# Test.net
KiCad netlist of a schematic drawn in EasyEDA Pro
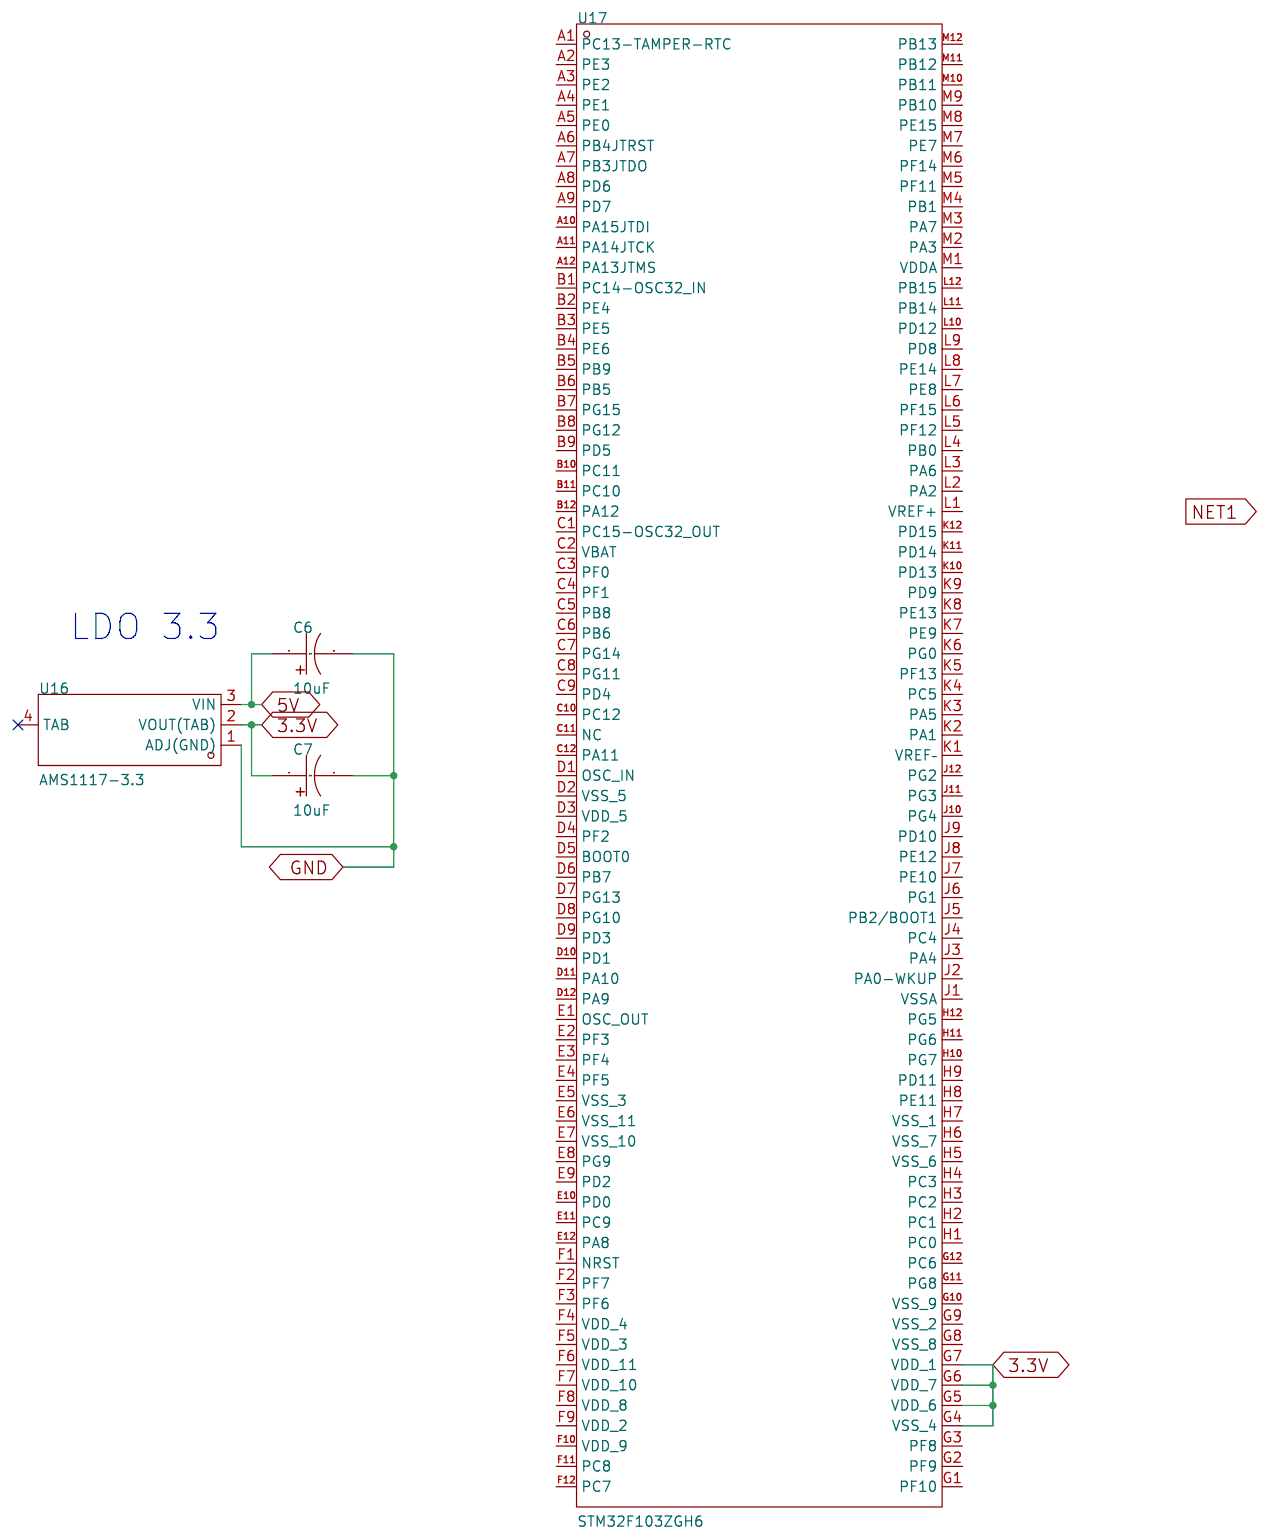
[diagram p0: schematic sheet]

(export (version "E")
  (design (tool "Eeschema 10.0.6"))
  (components
    (comp (ref "C6")
      (value "10uF")
      (footprint "easyedapro:CAP-SMD_BD4.0-L4.3-W4.3-FD-LS5.1")
      (fields (field (name "Manufacturer Part") "VSS100M1CTR-0404") (field (name "Manufacturer") "lelon(立隆)"))
      (libsource (lib "easyedapro") (part "VSS100M1C0404-TRO"))
    )
    (comp (ref "C7")
      (value "10uF")
      (footprint "easyedapro:CAP-SMD_BD4.0-L4.3-W4.3-FD-LS5.1")
      (fields (field (name "Manufacturer Part") "VSS100M1CTR-0404") (field (name "Manufacturer") "lelon(立隆)"))
      (libsource (lib "easyedapro") (part "VSS100M1C0404-TRO"))
    )
    (comp (ref "U16")
      (value "AMS1117-3.3")
      (footprint "easyedapro:SOT-223-4_L6.5-W3.5-P2.30-LS7.0-BR")
      (fields (field (name "Manufacturer") "UMW(友台半导体)"))
      (libsource (lib "easyedapro") (part "AMS1117-3.3_C347222"))
    )
    (comp (ref "U17")
      (value "STM32F103ZGH6")
      (footprint "easyedapro:CSPBGA-144_L10.0-W10.0-R12-C12-P0.80-TL")
      (fields (field (name "Manufacturer") "ST(意法半导体)"))
      (libsource (lib "easyedapro") (part "STM32F103ZGH6"))
    )
  )
  (nets
    (net (code "1") (name "3.3V") (class "Default")
      (node (ref "C7") (pin "1") (pinfunction "1_1") (pintype "unspecified"))
      (node (ref "U16") (pin "2") (pinfunction "VOUT(TAB)_2") (pintype "unspecified"))
      (node (ref "U17") (pin "G4") (pinfunction "VSS_4_G4") (pintype "unspecified"))
      (node (ref "U17") (pin "G5") (pinfunction "VDD_6_G5") (pintype "unspecified"))
      (node (ref "U17") (pin "G6") (pinfunction "VDD_7_G6") (pintype "unspecified"))
      (node (ref "U17") (pin "G7") (pinfunction "VDD_1_G7") (pintype "unspecified"))
    )
    (net (code "2") (name "5V") (class "Default")
      (node (ref "C6") (pin "1") (pinfunction "1_1") (pintype "unspecified"))
      (node (ref "U16") (pin "3") (pinfunction "VIN_3") (pintype "unspecified"))
    )
    (net (code "3") (name "GND") (class "Default")
      (node (ref "C6") (pin "2") (pinfunction "2_2") (pintype "unspecified"))
      (node (ref "C7") (pin "2") (pinfunction "2_2") (pintype "unspecified"))
      (node (ref "U16") (pin "1") (pinfunction "ADJ(GND)_1") (pintype "unspecified"))
    )
    (net (code "5") (name "unconnected-(U16-TAB-Pad4)") (class "Default")
      (node (ref "U16") (pin "4") (pinfunction "TAB_4") (pintype "unspecified+no_connect"))
    )
    (net (code "6") (name "unconnected-(U17-BOOT0-PadD5)") (class "Default")
      (node (ref "U17") (pin "D5") (pinfunction "BOOT0_D5") (pintype "unspecified"))
    )
    (net (code "7") (name "unconnected-(U17-NC-PadC11)") (class "Default")
      (node (ref "U17") (pin "C11") (pinfunction "NC_C11") (pintype "unspecified"))
    )
    (net (code "8") (name "unconnected-(U17-NRST-PadF1)") (class "Default")
      (node (ref "U17") (pin "F1") (pinfunction "NRST_F1") (pintype "unspecified"))
    )
    (net (code "9") (name "unconnected-(U17-OSC_IN-PadD1)") (class "Default")
      (node (ref "U17") (pin "D1") (pinfunction "OSC_IN_D1") (pintype "unspecified"))
    )
    (net (code "10") (name "unconnected-(U17-OSC_OUT-PadE1)") (class "Default")
      (node (ref "U17") (pin "E1") (pinfunction "OSC_OUT_E1") (pintype "unspecified"))
    )
    (net (code "11") (name "unconnected-(U17-PA0-WKUP-PadJ2)") (class "Default")
      (node (ref "U17") (pin "J2") (pinfunction "PA0-WKUP_J2") (pintype "unspecified"))
    )
    (net (code "12") (name "unconnected-(U17-PA1-PadK2)") (class "Default")
      (node (ref "U17") (pin "K2") (pinfunction "PA1_K2") (pintype "unspecified"))
    )
    (net (code "13") (name "unconnected-(U17-PA2-PadL2)") (class "Default")
      (node (ref "U17") (pin "L2") (pinfunction "PA2_L2") (pintype "unspecified"))
    )
    (net (code "14") (name "unconnected-(U17-PA3-PadM2)") (class "Default")
      (node (ref "U17") (pin "M2") (pinfunction "PA3_M2") (pintype "unspecified"))
    )
    (net (code "15") (name "unconnected-(U17-PA4-PadJ3)") (class "Default")
      (node (ref "U17") (pin "J3") (pinfunction "PA4_J3") (pintype "unspecified"))
    )
    (net (code "16") (name "unconnected-(U17-PA5-PadK3)") (class "Default")
      (node (ref "U17") (pin "K3") (pinfunction "PA5_K3") (pintype "unspecified"))
    )
    (net (code "17") (name "unconnected-(U17-PA6-PadL3)") (class "Default")
      (node (ref "U17") (pin "L3") (pinfunction "PA6_L3") (pintype "unspecified"))
    )
    (net (code "18") (name "unconnected-(U17-PA7-PadM3)") (class "Default")
      (node (ref "U17") (pin "M3") (pinfunction "PA7_M3") (pintype "unspecified"))
    )
    (net (code "19") (name "unconnected-(U17-PA8-PadE12)") (class "Default")
      (node (ref "U17") (pin "E12") (pinfunction "PA8_E12") (pintype "unspecified"))
    )
    (net (code "20") (name "unconnected-(U17-PA9-PadD12)") (class "Default")
      (node (ref "U17") (pin "D12") (pinfunction "PA9_D12") (pintype "unspecified"))
    )
    (net (code "21") (name "unconnected-(U17-PA10-PadD11)") (class "Default")
      (node (ref "U17") (pin "D11") (pinfunction "PA10_D11") (pintype "unspecified"))
    )
    (net (code "22") (name "unconnected-(U17-PA11-PadC12)") (class "Default")
      (node (ref "U17") (pin "C12") (pinfunction "PA11_C12") (pintype "unspecified"))
    )
    (net (code "23") (name "unconnected-(U17-PA12-PadB12)") (class "Default")
      (node (ref "U17") (pin "B12") (pinfunction "PA12_B12") (pintype "unspecified"))
    )
    (net (code "24") (name "unconnected-(U17-PA13JTMS-PadA12)") (class "Default")
      (node (ref "U17") (pin "A12") (pinfunction "PA13JTMS_A12") (pintype "unspecified"))
    )
    (net (code "25") (name "unconnected-(U17-PA14JTCK-PadA11)") (class "Default")
      (node (ref "U17") (pin "A11") (pinfunction "PA14JTCK_A11") (pintype "unspecified"))
    )
    (net (code "26") (name "unconnected-(U17-PA15JTDI-PadA10)") (class "Default")
      (node (ref "U17") (pin "A10") (pinfunction "PA15JTDI_A10") (pintype "unspecified"))
    )
    (net (code "27") (name "unconnected-(U17-PB0-PadL4)") (class "Default")
      (node (ref "U17") (pin "L4") (pinfunction "PB0_L4") (pintype "unspecified"))
    )
    (net (code "28") (name "unconnected-(U17-PB1-PadM4)") (class "Default")
      (node (ref "U17") (pin "M4") (pinfunction "PB1_M4") (pintype "unspecified"))
    )
    (net (code "29") (name "unconnected-(U17-PB2{slash}BOOT1-PadJ5)") (class "Default")
      (node (ref "U17") (pin "J5") (pinfunction "PB2/BOOT1_J5") (pintype "unspecified"))
    )
    (net (code "30") (name "unconnected-(U17-PB3JTDO-PadA7)") (class "Default")
      (node (ref "U17") (pin "A7") (pinfunction "PB3JTDO_A7") (pintype "unspecified"))
    )
    (net (code "31") (name "unconnected-(U17-PB4JTRST-PadA6)") (class "Default")
      (node (ref "U17") (pin "A6") (pinfunction "PB4JTRST_A6") (pintype "unspecified"))
    )
    (net (code "32") (name "unconnected-(U17-PB5-PadB6)") (class "Default")
      (node (ref "U17") (pin "B6") (pinfunction "PB5_B6") (pintype "unspecified"))
    )
    (net (code "33") (name "unconnected-(U17-PB6-PadC6)") (class "Default")
      (node (ref "U17") (pin "C6") (pinfunction "PB6_C6") (pintype "unspecified"))
    )
    (net (code "34") (name "unconnected-(U17-PB7-PadD6)") (class "Default")
      (node (ref "U17") (pin "D6") (pinfunction "PB7_D6") (pintype "unspecified"))
    )
    (net (code "35") (name "unconnected-(U17-PB8-PadC5)") (class "Default")
      (node (ref "U17") (pin "C5") (pinfunction "PB8_C5") (pintype "unspecified"))
    )
    (net (code "36") (name "unconnected-(U17-PB9-PadB5)") (class "Default")
      (node (ref "U17") (pin "B5") (pinfunction "PB9_B5") (pintype "unspecified"))
    )
    (net (code "37") (name "unconnected-(U17-PB10-PadM9)") (class "Default")
      (node (ref "U17") (pin "M9") (pinfunction "PB10_M9") (pintype "unspecified"))
    )
    (net (code "38") (name "unconnected-(U17-PB11-PadM10)") (class "Default")
      (node (ref "U17") (pin "M10") (pinfunction "PB11_M10") (pintype "unspecified"))
    )
    (net (code "39") (name "unconnected-(U17-PB12-PadM11)") (class "Default")
      (node (ref "U17") (pin "M11") (pinfunction "PB12_M11") (pintype "unspecified"))
    )
    (net (code "40") (name "unconnected-(U17-PB13-PadM12)") (class "Default")
      (node (ref "U17") (pin "M12") (pinfunction "PB13_M12") (pintype "unspecified"))
    )
    (net (code "41") (name "unconnected-(U17-PB14-PadL11)") (class "Default")
      (node (ref "U17") (pin "L11") (pinfunction "PB14_L11") (pintype "unspecified"))
    )
    (net (code "42") (name "unconnected-(U17-PB15-PadL12)") (class "Default")
      (node (ref "U17") (pin "L12") (pinfunction "PB15_L12") (pintype "unspecified"))
    )
    (net (code "43") (name "unconnected-(U17-PC0-PadH1)") (class "Default")
      (node (ref "U17") (pin "H1") (pinfunction "PC0_H1") (pintype "unspecified"))
    )
    (net (code "44") (name "unconnected-(U17-PC1-PadH2)") (class "Default")
      (node (ref "U17") (pin "H2") (pinfunction "PC1_H2") (pintype "unspecified"))
    )
    (net (code "45") (name "unconnected-(U17-PC2-PadH3)") (class "Default")
      (node (ref "U17") (pin "H3") (pinfunction "PC2_H3") (pintype "unspecified"))
    )
    (net (code "46") (name "unconnected-(U17-PC3-PadH4)") (class "Default")
      (node (ref "U17") (pin "H4") (pinfunction "PC3_H4") (pintype "unspecified"))
    )
    (net (code "47") (name "unconnected-(U17-PC4-PadJ4)") (class "Default")
      (node (ref "U17") (pin "J4") (pinfunction "PC4_J4") (pintype "unspecified"))
    )
    (net (code "48") (name "unconnected-(U17-PC5-PadK4)") (class "Default")
      (node (ref "U17") (pin "K4") (pinfunction "PC5_K4") (pintype "unspecified"))
    )
    (net (code "49") (name "unconnected-(U17-PC6-PadG12)") (class "Default")
      (node (ref "U17") (pin "G12") (pinfunction "PC6_G12") (pintype "unspecified"))
    )
    (net (code "50") (name "unconnected-(U17-PC7-PadF12)") (class "Default")
      (node (ref "U17") (pin "F12") (pinfunction "PC7_F12") (pintype "unspecified"))
    )
    (net (code "51") (name "unconnected-(U17-PC8-PadF11)") (class "Default")
      (node (ref "U17") (pin "F11") (pinfunction "PC8_F11") (pintype "unspecified"))
    )
    (net (code "52") (name "unconnected-(U17-PC9-PadE11)") (class "Default")
      (node (ref "U17") (pin "E11") (pinfunction "PC9_E11") (pintype "unspecified"))
    )
    (net (code "53") (name "unconnected-(U17-PC10-PadB11)") (class "Default")
      (node (ref "U17") (pin "B11") (pinfunction "PC10_B11") (pintype "unspecified"))
    )
    (net (code "54") (name "unconnected-(U17-PC11-PadB10)") (class "Default")
      (node (ref "U17") (pin "B10") (pinfunction "PC11_B10") (pintype "unspecified"))
    )
    (net (code "55") (name "unconnected-(U17-PC12-PadC10)") (class "Default")
      (node (ref "U17") (pin "C10") (pinfunction "PC12_C10") (pintype "unspecified"))
    )
    (net (code "56") (name "unconnected-(U17-PC13-TAMPER-RTC-PadA1)") (class "Default")
      (node (ref "U17") (pin "A1") (pinfunction "PC13-TAMPER-RTC_A1") (pintype "unspecified"))
    )
    (net (code "57") (name "unconnected-(U17-PC14-OSC32_IN-PadB1)") (class "Default")
      (node (ref "U17") (pin "B1") (pinfunction "PC14-OSC32_IN_B1") (pintype "unspecified"))
    )
    (net (code "58") (name "unconnected-(U17-PC15-OSC32_OUT-PadC1)") (class "Default")
      (node (ref "U17") (pin "C1") (pinfunction "PC15-OSC32_OUT_C1") (pintype "unspecified"))
    )
    (net (code "59") (name "unconnected-(U17-PD0-PadE10)") (class "Default")
      (node (ref "U17") (pin "E10") (pinfunction "PD0_E10") (pintype "unspecified"))
    )
    (net (code "60") (name "unconnected-(U17-PD1-PadD10)") (class "Default")
      (node (ref "U17") (pin "D10") (pinfunction "PD1_D10") (pintype "unspecified"))
    )
    (net (code "61") (name "unconnected-(U17-PD2-PadE9)") (class "Default")
      (node (ref "U17") (pin "E9") (pinfunction "PD2_E9") (pintype "unspecified"))
    )
    (net (code "62") (name "unconnected-(U17-PD3-PadD9)") (class "Default")
      (node (ref "U17") (pin "D9") (pinfunction "PD3_D9") (pintype "unspecified"))
    )
    (net (code "63") (name "unconnected-(U17-PD4-PadC9)") (class "Default")
      (node (ref "U17") (pin "C9") (pinfunction "PD4_C9") (pintype "unspecified"))
    )
    (net (code "64") (name "unconnected-(U17-PD5-PadB9)") (class "Default")
      (node (ref "U17") (pin "B9") (pinfunction "PD5_B9") (pintype "unspecified"))
    )
    (net (code "65") (name "unconnected-(U17-PD6-PadA8)") (class "Default")
      (node (ref "U17") (pin "A8") (pinfunction "PD6_A8") (pintype "unspecified"))
    )
    (net (code "66") (name "unconnected-(U17-PD7-PadA9)") (class "Default")
      (node (ref "U17") (pin "A9") (pinfunction "PD7_A9") (pintype "unspecified"))
    )
    (net (code "67") (name "unconnected-(U17-PD8-PadL9)") (class "Default")
      (node (ref "U17") (pin "L9") (pinfunction "PD8_L9") (pintype "unspecified"))
    )
    (net (code "68") (name "unconnected-(U17-PD9-PadK9)") (class "Default")
      (node (ref "U17") (pin "K9") (pinfunction "PD9_K9") (pintype "unspecified"))
    )
    (net (code "69") (name "unconnected-(U17-PD10-PadJ9)") (class "Default")
      (node (ref "U17") (pin "J9") (pinfunction "PD10_J9") (pintype "unspecified"))
    )
    (net (code "70") (name "unconnected-(U17-PD11-PadH9)") (class "Default")
      (node (ref "U17") (pin "H9") (pinfunction "PD11_H9") (pintype "unspecified"))
    )
    (net (code "71") (name "unconnected-(U17-PD12-PadL10)") (class "Default")
      (node (ref "U17") (pin "L10") (pinfunction "PD12_L10") (pintype "unspecified"))
    )
    (net (code "72") (name "unconnected-(U17-PD13-PadK10)") (class "Default")
      (node (ref "U17") (pin "K10") (pinfunction "PD13_K10") (pintype "unspecified"))
    )
    (net (code "73") (name "unconnected-(U17-PD14-PadK11)") (class "Default")
      (node (ref "U17") (pin "K11") (pinfunction "PD14_K11") (pintype "unspecified"))
    )
    (net (code "74") (name "unconnected-(U17-PD15-PadK12)") (class "Default")
      (node (ref "U17") (pin "K12") (pinfunction "PD15_K12") (pintype "unspecified"))
    )
    (net (code "75") (name "unconnected-(U17-PE0-PadA5)") (class "Default")
      (node (ref "U17") (pin "A5") (pinfunction "PE0_A5") (pintype "unspecified"))
    )
    (net (code "76") (name "unconnected-(U17-PE1-PadA4)") (class "Default")
      (node (ref "U17") (pin "A4") (pinfunction "PE1_A4") (pintype "unspecified"))
    )
    (net (code "77") (name "unconnected-(U17-PE2-PadA3)") (class "Default")
      (node (ref "U17") (pin "A3") (pinfunction "PE2_A3") (pintype "unspecified"))
    )
    (net (code "78") (name "unconnected-(U17-PE3-PadA2)") (class "Default")
      (node (ref "U17") (pin "A2") (pinfunction "PE3_A2") (pintype "unspecified"))
    )
    (net (code "79") (name "unconnected-(U17-PE4-PadB2)") (class "Default")
      (node (ref "U17") (pin "B2") (pinfunction "PE4_B2") (pintype "unspecified"))
    )
    (net (code "80") (name "unconnected-(U17-PE5-PadB3)") (class "Default")
      (node (ref "U17") (pin "B3") (pinfunction "PE5_B3") (pintype "unspecified"))
    )
    (net (code "81") (name "unconnected-(U17-PE6-PadB4)") (class "Default")
      (node (ref "U17") (pin "B4") (pinfunction "PE6_B4") (pintype "unspecified"))
    )
    (net (code "82") (name "unconnected-(U17-PE7-PadM7)") (class "Default")
      (node (ref "U17") (pin "M7") (pinfunction "PE7_M7") (pintype "unspecified"))
    )
    (net (code "83") (name "unconnected-(U17-PE8-PadL7)") (class "Default")
      (node (ref "U17") (pin "L7") (pinfunction "PE8_L7") (pintype "unspecified"))
    )
    (net (code "84") (name "unconnected-(U17-PE9-PadK7)") (class "Default")
      (node (ref "U17") (pin "K7") (pinfunction "PE9_K7") (pintype "unspecified"))
    )
    (net (code "85") (name "unconnected-(U17-PE10-PadJ7)") (class "Default")
      (node (ref "U17") (pin "J7") (pinfunction "PE10_J7") (pintype "unspecified"))
    )
    (net (code "86") (name "unconnected-(U17-PE11-PadH8)") (class "Default")
      (node (ref "U17") (pin "H8") (pinfunction "PE11_H8") (pintype "unspecified"))
    )
    (net (code "87") (name "unconnected-(U17-PE12-PadJ8)") (class "Default")
      (node (ref "U17") (pin "J8") (pinfunction "PE12_J8") (pintype "unspecified"))
    )
    (net (code "88") (name "unconnected-(U17-PE13-PadK8)") (class "Default")
      (node (ref "U17") (pin "K8") (pinfunction "PE13_K8") (pintype "unspecified"))
    )
    (net (code "89") (name "unconnected-(U17-PE14-PadL8)") (class "Default")
      (node (ref "U17") (pin "L8") (pinfunction "PE14_L8") (pintype "unspecified"))
    )
    (net (code "90") (name "unconnected-(U17-PE15-PadM8)") (class "Default")
      (node (ref "U17") (pin "M8") (pinfunction "PE15_M8") (pintype "unspecified"))
    )
    (net (code "91") (name "unconnected-(U17-PF0-PadC3)") (class "Default")
      (node (ref "U17") (pin "C3") (pinfunction "PF0_C3") (pintype "unspecified"))
    )
    (net (code "92") (name "unconnected-(U17-PF1-PadC4)") (class "Default")
      (node (ref "U17") (pin "C4") (pinfunction "PF1_C4") (pintype "unspecified"))
    )
    (net (code "93") (name "unconnected-(U17-PF2-PadD4)") (class "Default")
      (node (ref "U17") (pin "D4") (pinfunction "PF2_D4") (pintype "unspecified"))
    )
    (net (code "94") (name "unconnected-(U17-PF3-PadE2)") (class "Default")
      (node (ref "U17") (pin "E2") (pinfunction "PF3_E2") (pintype "unspecified"))
    )
    (net (code "95") (name "unconnected-(U17-PF4-PadE3)") (class "Default")
      (node (ref "U17") (pin "E3") (pinfunction "PF4_E3") (pintype "unspecified"))
    )
    (net (code "96") (name "unconnected-(U17-PF5-PadE4)") (class "Default")
      (node (ref "U17") (pin "E4") (pinfunction "PF5_E4") (pintype "unspecified"))
    )
    (net (code "97") (name "unconnected-(U17-PF6-PadF3)") (class "Default")
      (node (ref "U17") (pin "F3") (pinfunction "PF6_F3") (pintype "unspecified"))
    )
    (net (code "98") (name "unconnected-(U17-PF7-PadF2)") (class "Default")
      (node (ref "U17") (pin "F2") (pinfunction "PF7_F2") (pintype "unspecified"))
    )
    (net (code "99") (name "unconnected-(U17-PF8-PadG3)") (class "Default")
      (node (ref "U17") (pin "G3") (pinfunction "PF8_G3") (pintype "unspecified"))
    )
    (net (code "100") (name "unconnected-(U17-PF9-PadG2)") (class "Default")
      (node (ref "U17") (pin "G2") (pinfunction "PF9_G2") (pintype "unspecified"))
    )
    (net (code "101") (name "unconnected-(U17-PF10-PadG1)") (class "Default")
      (node (ref "U17") (pin "G1") (pinfunction "PF10_G1") (pintype "unspecified"))
    )
    (net (code "102") (name "unconnected-(U17-PF11-PadM5)") (class "Default")
      (node (ref "U17") (pin "M5") (pinfunction "PF11_M5") (pintype "unspecified"))
    )
    (net (code "103") (name "unconnected-(U17-PF12-PadL5)") (class "Default")
      (node (ref "U17") (pin "L5") (pinfunction "PF12_L5") (pintype "unspecified"))
    )
    (net (code "104") (name "unconnected-(U17-PF13-PadK5)") (class "Default")
      (node (ref "U17") (pin "K5") (pinfunction "PF13_K5") (pintype "unspecified"))
    )
    (net (code "105") (name "unconnected-(U17-PF14-PadM6)") (class "Default")
      (node (ref "U17") (pin "M6") (pinfunction "PF14_M6") (pintype "unspecified"))
    )
    (net (code "106") (name "unconnected-(U17-PF15-PadL6)") (class "Default")
      (node (ref "U17") (pin "L6") (pinfunction "PF15_L6") (pintype "unspecified"))
    )
    (net (code "107") (name "unconnected-(U17-PG0-PadK6)") (class "Default")
      (node (ref "U17") (pin "K6") (pinfunction "PG0_K6") (pintype "unspecified"))
    )
    (net (code "108") (name "unconnected-(U17-PG1-PadJ6)") (class "Default")
      (node (ref "U17") (pin "J6") (pinfunction "PG1_J6") (pintype "unspecified"))
    )
    (net (code "109") (name "unconnected-(U17-PG2-PadJ12)") (class "Default")
      (node (ref "U17") (pin "J12") (pinfunction "PG2_J12") (pintype "unspecified"))
    )
    (net (code "110") (name "unconnected-(U17-PG3-PadJ11)") (class "Default")
      (node (ref "U17") (pin "J11") (pinfunction "PG3_J11") (pintype "unspecified"))
    )
    (net (code "111") (name "unconnected-(U17-PG4-PadJ10)") (class "Default")
      (node (ref "U17") (pin "J10") (pinfunction "PG4_J10") (pintype "unspecified"))
    )
    (net (code "112") (name "unconnected-(U17-PG5-PadH12)") (class "Default")
      (node (ref "U17") (pin "H12") (pinfunction "PG5_H12") (pintype "unspecified"))
    )
    (net (code "113") (name "unconnected-(U17-PG6-PadH11)") (class "Default")
      (node (ref "U17") (pin "H11") (pinfunction "PG6_H11") (pintype "unspecified"))
    )
    (net (code "114") (name "unconnected-(U17-PG7-PadH10)") (class "Default")
      (node (ref "U17") (pin "H10") (pinfunction "PG7_H10") (pintype "unspecified"))
    )
    (net (code "115") (name "unconnected-(U17-PG8-PadG11)") (class "Default")
      (node (ref "U17") (pin "G11") (pinfunction "PG8_G11") (pintype "unspecified"))
    )
    (net (code "116") (name "unconnected-(U17-PG9-PadE8)") (class "Default")
      (node (ref "U17") (pin "E8") (pinfunction "PG9_E8") (pintype "unspecified"))
    )
    (net (code "117") (name "unconnected-(U17-PG10-PadD8)") (class "Default")
      (node (ref "U17") (pin "D8") (pinfunction "PG10_D8") (pintype "unspecified"))
    )
    (net (code "118") (name "unconnected-(U17-PG11-PadC8)") (class "Default")
      (node (ref "U17") (pin "C8") (pinfunction "PG11_C8") (pintype "unspecified"))
    )
    (net (code "119") (name "unconnected-(U17-PG12-PadB8)") (class "Default")
      (node (ref "U17") (pin "B8") (pinfunction "PG12_B8") (pintype "unspecified"))
    )
    (net (code "120") (name "unconnected-(U17-PG13-PadD7)") (class "Default")
      (node (ref "U17") (pin "D7") (pinfunction "PG13_D7") (pintype "unspecified"))
    )
    (net (code "121") (name "unconnected-(U17-PG14-PadC7)") (class "Default")
      (node (ref "U17") (pin "C7") (pinfunction "PG14_C7") (pintype "unspecified"))
    )
    (net (code "122") (name "unconnected-(U17-PG15-PadB7)") (class "Default")
      (node (ref "U17") (pin "B7") (pinfunction "PG15_B7") (pintype "unspecified"))
    )
    (net (code "123") (name "unconnected-(U17-VBAT-PadC2)") (class "Default")
      (node (ref "U17") (pin "C2") (pinfunction "VBAT_C2") (pintype "unspecified"))
    )
    (net (code "124") (name "unconnected-(U17-VDDA-PadM1)") (class "Default")
      (node (ref "U17") (pin "M1") (pinfunction "VDDA_M1") (pintype "unspecified"))
    )
    (net (code "125") (name "unconnected-(U17-VDD_2-PadF9)") (class "Default")
      (node (ref "U17") (pin "F9") (pinfunction "VDD_2_F9") (pintype "unspecified"))
    )
    (net (code "126") (name "unconnected-(U17-VDD_3-PadF5)") (class "Default")
      (node (ref "U17") (pin "F5") (pinfunction "VDD_3_F5") (pintype "unspecified"))
    )
    (net (code "127") (name "unconnected-(U17-VDD_4-PadF4)") (class "Default")
      (node (ref "U17") (pin "F4") (pinfunction "VDD_4_F4") (pintype "unspecified"))
    )
    (net (code "128") (name "unconnected-(U17-VDD_5-PadD3)") (class "Default")
      (node (ref "U17") (pin "D3") (pinfunction "VDD_5_D3") (pintype "unspecified"))
    )
    (net (code "129") (name "unconnected-(U17-VDD_8-PadF8)") (class "Default")
      (node (ref "U17") (pin "F8") (pinfunction "VDD_8_F8") (pintype "unspecified"))
    )
    (net (code "130") (name "unconnected-(U17-VDD_9-PadF10)") (class "Default")
      (node (ref "U17") (pin "F10") (pinfunction "VDD_9_F10") (pintype "unspecified"))
    )
    (net (code "131") (name "unconnected-(U17-VDD_10-PadF7)") (class "Default")
      (node (ref "U17") (pin "F7") (pinfunction "VDD_10_F7") (pintype "unspecified"))
    )
    (net (code "132") (name "unconnected-(U17-VDD_11-PadF6)") (class "Default")
      (node (ref "U17") (pin "F6") (pinfunction "VDD_11_F6") (pintype "unspecified"))
    )
    (net (code "133") (name "unconnected-(U17-VREF+-PadL1)") (class "Default")
      (node (ref "U17") (pin "L1") (pinfunction "VREF+_L1") (pintype "unspecified"))
    )
    (net (code "134") (name "unconnected-(U17-VREF–-PadK1)") (class "Default")
      (node (ref "U17") (pin "K1") (pinfunction "VREF–_K1") (pintype "unspecified"))
    )
    (net (code "135") (name "unconnected-(U17-VSSA-PadJ1)") (class "Default")
      (node (ref "U17") (pin "J1") (pinfunction "VSSA_J1") (pintype "unspecified"))
    )
    (net (code "136") (name "unconnected-(U17-VSS_1-PadH7)") (class "Default")
      (node (ref "U17") (pin "H7") (pinfunction "VSS_1_H7") (pintype "unspecified"))
    )
    (net (code "137") (name "unconnected-(U17-VSS_2-PadG9)") (class "Default")
      (node (ref "U17") (pin "G9") (pinfunction "VSS_2_G9") (pintype "unspecified"))
    )
    (net (code "138") (name "unconnected-(U17-VSS_3-PadE5)") (class "Default")
      (node (ref "U17") (pin "E5") (pinfunction "VSS_3_E5") (pintype "unspecified"))
    )
    (net (code "139") (name "unconnected-(U17-VSS_5-PadD2)") (class "Default")
      (node (ref "U17") (pin "D2") (pinfunction "VSS_5_D2") (pintype "unspecified"))
    )
    (net (code "140") (name "unconnected-(U17-VSS_6-PadH5)") (class "Default")
      (node (ref "U17") (pin "H5") (pinfunction "VSS_6_H5") (pintype "unspecified"))
    )
    (net (code "141") (name "unconnected-(U17-VSS_7-PadH6)") (class "Default")
      (node (ref "U17") (pin "H6") (pinfunction "VSS_7_H6") (pintype "unspecified"))
    )
    (net (code "142") (name "unconnected-(U17-VSS_8-PadG8)") (class "Default")
      (node (ref "U17") (pin "G8") (pinfunction "VSS_8_G8") (pintype "unspecified"))
    )
    (net (code "143") (name "unconnected-(U17-VSS_9-PadG10)") (class "Default")
      (node (ref "U17") (pin "G10") (pinfunction "VSS_9_G10") (pintype "unspecified"))
    )
    (net (code "144") (name "unconnected-(U17-VSS_10-PadE7)") (class "Default")
      (node (ref "U17") (pin "E7") (pinfunction "VSS_10_E7") (pintype "unspecified"))
    )
    (net (code "145") (name "unconnected-(U17-VSS_11-PadE6)") (class "Default")
      (node (ref "U17") (pin "E6") (pinfunction "VSS_11_E6") (pintype "unspecified"))
    )
  )
)
